# MazeBoard.net
KiCad netlist of a schematic drawn in EAGLE
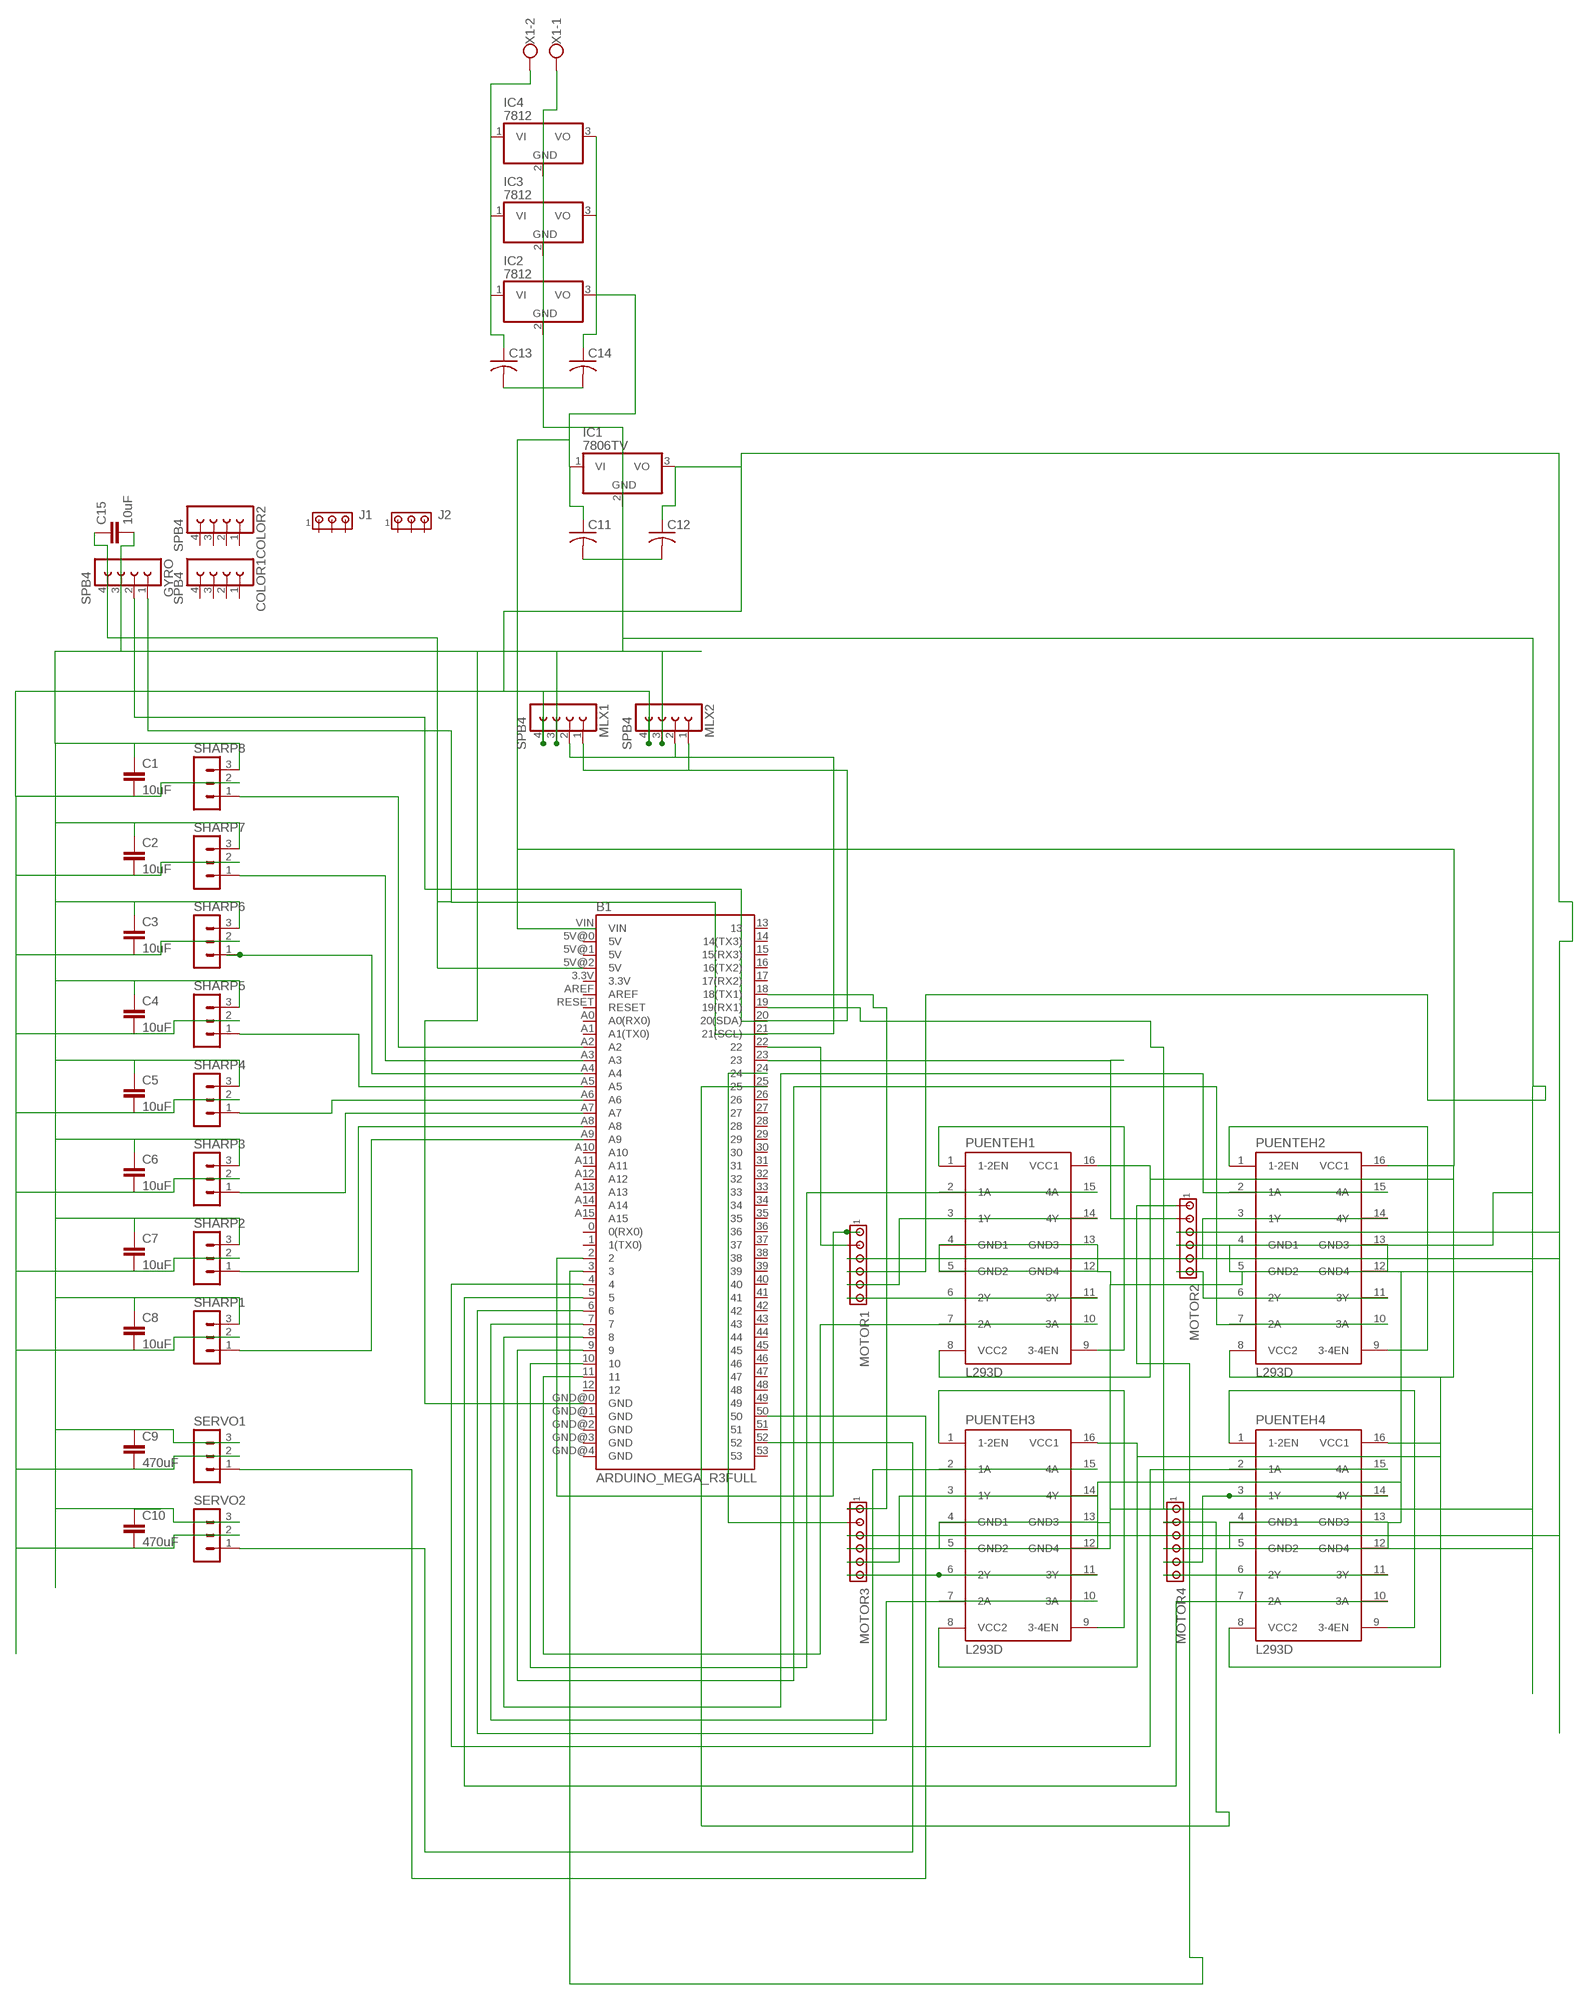
[diagram p0: schematic, sheet 1]

(export (version "E")
  (design (tool "Eeschema 10.0.6"))
  (components
    (comp (ref "B1")
      (value "ARDUINO_MEGA_R3FULL")
      (footprint "eagle-import:ARDUINO_MEGA")
      (libsource (lib "eagle-import") (part "ARDUINO_MEGA_R3FULL"))
    )
    (comp (ref "C1")
      (value "10uF")
      (footprint "eagle-import:C2.5-3")
      (libsource (lib "eagle-import") (part "C2,5-3"))
    )
    (comp (ref "C2")
      (value "10uF")
      (footprint "eagle-import:C2.5-3")
      (libsource (lib "eagle-import") (part "C2,5-3"))
    )
    (comp (ref "C3")
      (value "10uF")
      (footprint "eagle-import:C2.5-3")
      (libsource (lib "eagle-import") (part "C2,5-3"))
    )
    (comp (ref "C4")
      (value "10uF")
      (footprint "eagle-import:C2.5-3")
      (libsource (lib "eagle-import") (part "C2,5-3"))
    )
    (comp (ref "C5")
      (value "10uF")
      (footprint "eagle-import:C2.5-3")
      (libsource (lib "eagle-import") (part "C2,5-3"))
    )
    (comp (ref "C6")
      (value "10uF")
      (footprint "eagle-import:C2.5-3")
      (libsource (lib "eagle-import") (part "C2,5-3"))
    )
    (comp (ref "C7")
      (value "10uF")
      (footprint "eagle-import:C2.5-3")
      (libsource (lib "eagle-import") (part "C2,5-3"))
    )
    (comp (ref "C8")
      (value "10uF")
      (footprint "eagle-import:C2.5-3")
      (libsource (lib "eagle-import") (part "C2,5-3"))
    )
    (comp (ref "C9")
      (value "470uF")
      (footprint "eagle-import:C2.5-3")
      (libsource (lib "eagle-import") (part "C2,5-3"))
    )
    (comp (ref "C10")
      (value "470uF")
      (footprint "eagle-import:C2.5-3")
      (libsource (lib "eagle-import") (part "C2,5-3"))
    )
    (comp (ref "C11")
      (value "C-US025-024X044")
      (footprint "eagle-import:C025-024X044")
      (libsource (lib "eagle-import") (part "C-US025-024X044"))
    )
    (comp (ref "C12")
      (value "C-US025-024X044")
      (footprint "eagle-import:C025-024X044")
      (libsource (lib "eagle-import") (part "C-US025-024X044"))
    )
    (comp (ref "C13")
      (value "C-US025-024X044")
      (footprint "eagle-import:C025-024X044")
      (libsource (lib "eagle-import") (part "C-US025-024X044"))
    )
    (comp (ref "C14")
      (value "C-US025-024X044")
      (footprint "eagle-import:C025-024X044")
      (libsource (lib "eagle-import") (part "C-US025-024X044"))
    )
    (comp (ref "C15")
      (value "10uF")
      (footprint "eagle-import:C2.5-3")
      (libsource (lib "eagle-import") (part "C2,5-3"))
    )
    (comp (ref "COLOR1")
      (value "SPB4")
      (footprint "eagle-import:SPB4")
      (libsource (lib "eagle-import") (part "SPB4"))
    )
    (comp (ref "COLOR2")
      (value "SPB4")
      (footprint "eagle-import:SPB4")
      (libsource (lib "eagle-import") (part "SPB4"))
    )
    (comp (ref "GYRO")
      (value "SPB4")
      (footprint "eagle-import:SPB4")
      (libsource (lib "eagle-import") (part "SPB4"))
    )
    (comp (ref "IC1")
      (value "7806TV")
      (footprint "eagle-import:TO220V")
      (libsource (lib "eagle-import") (part "78TV05"))
    )
    (comp (ref "IC2")
      (value "7812")
      (footprint "eagle-import:TO220V")
      (libsource (lib "eagle-import") (part "78TV05"))
    )
    (comp (ref "IC3")
      (value "7812")
      (footprint "eagle-import:TO220V")
      (libsource (lib "eagle-import") (part "78TV05"))
    )
    (comp (ref "IC4")
      (value "7812")
      (footprint "eagle-import:TO220V")
      (libsource (lib "eagle-import") (part "78TV05"))
    )
    (comp (ref "J1")
      (value "MTA03-100")
      (footprint "eagle-import:10X03MTA")
      (libsource (lib "eagle-import") (part "MTA03-100"))
    )
    (comp (ref "J2")
      (value "MTA03-100")
      (footprint "eagle-import:10X03MTA")
      (libsource (lib "eagle-import") (part "MTA03-100"))
    )
    (comp (ref "MLX1")
      (value "SPB4")
      (footprint "eagle-import:SPB4")
      (libsource (lib "eagle-import") (part "SPB4"))
    )
    (comp (ref "MLX2")
      (value "SPB4")
      (footprint "eagle-import:SPB4")
      (libsource (lib "eagle-import") (part "SPB4"))
    )
    (comp (ref "MOTOR1")
      (value "MTA06-100")
      (footprint "eagle-import:10X06MTA")
      (libsource (lib "eagle-import") (part "MTA06-100"))
    )
    (comp (ref "MOTOR2")
      (value "MTA06-100")
      (footprint "eagle-import:10X06MTA")
      (libsource (lib "eagle-import") (part "MTA06-100"))
    )
    (comp (ref "MOTOR3")
      (value "MTA06-100")
      (footprint "eagle-import:10X06MTA")
      (libsource (lib "eagle-import") (part "MTA06-100"))
    )
    (comp (ref "MOTOR4")
      (value "MTA06-100")
      (footprint "eagle-import:10X06MTA")
      (libsource (lib "eagle-import") (part "MTA06-100"))
    )
    (comp (ref "PUENTEH1")
      (value "L293D")
      (footprint "eagle-import:DIL16")
      (libsource (lib "eagle-import") (part "L293D"))
    )
    (comp (ref "PUENTEH2")
      (value "L293D")
      (footprint "eagle-import:DIL16")
      (libsource (lib "eagle-import") (part "L293D"))
    )
    (comp (ref "PUENTEH3")
      (value "L293D")
      (footprint "eagle-import:DIL16")
      (libsource (lib "eagle-import") (part "L293D"))
    )
    (comp (ref "PUENTEH4")
      (value "L293D")
      (footprint "eagle-import:DIL16")
      (libsource (lib "eagle-import") (part "L293D"))
    )
    (comp (ref "SERVO1")
      (value "MA03-1")
      (footprint "eagle-import:MA03-1")
      (libsource (lib "eagle-import") (part "MA03-1"))
    )
    (comp (ref "SERVO2")
      (value "MA03-1")
      (footprint "eagle-import:MA03-1")
      (libsource (lib "eagle-import") (part "MA03-1"))
    )
    (comp (ref "SHARP1")
      (value "MA03-1")
      (footprint "eagle-import:MA03-1")
      (libsource (lib "eagle-import") (part "MA03-1"))
    )
    (comp (ref "SHARP2")
      (value "MA03-1")
      (footprint "eagle-import:MA03-1")
      (libsource (lib "eagle-import") (part "MA03-1"))
    )
    (comp (ref "SHARP3")
      (value "MA03-1")
      (footprint "eagle-import:MA03-1")
      (libsource (lib "eagle-import") (part "MA03-1"))
    )
    (comp (ref "SHARP4")
      (value "MA03-1")
      (footprint "eagle-import:MA03-1")
      (libsource (lib "eagle-import") (part "MA03-1"))
    )
    (comp (ref "SHARP5")
      (value "MA03-1")
      (footprint "eagle-import:MA03-1")
      (libsource (lib "eagle-import") (part "MA03-1"))
    )
    (comp (ref "SHARP6")
      (value "MA03-1")
      (footprint "eagle-import:MA03-1")
      (libsource (lib "eagle-import") (part "MA03-1"))
    )
    (comp (ref "SHARP7")
      (value "MA03-1")
      (footprint "eagle-import:MA03-1")
      (libsource (lib "eagle-import") (part "MA03-1"))
    )
    (comp (ref "SHARP8")
      (value "MA03-1")
      (footprint "eagle-import:MA03-1")
      (libsource (lib "eagle-import") (part "MA03-1"))
    )
    (comp (ref "X1")
      (value "W237-102")
      (footprint "eagle-import:W237-102")
      (fields (field (name "MPN") "237-102"))
      (libsource (lib "eagle-import") (part "W237-102"))
    )
  )
  (nets
    (net (code "1") (name "Net-(B1-5V-Pad5V@2)") (class "Default")
      (node (ref "B1") (pin "5V@2") (pinfunction "5V_5V@2") (pintype "bidirectional"))
      (node (ref "C15") (pin "1") (pinfunction "1_1") (pintype "passive"))
      (node (ref "GYRO") (pin "4") (pinfunction "4_4") (pintype "passive"))
    )
    (net (code "2") (name "Net-(B1-18(TX1))") (class "Default")
      (node (ref "B1") (pin "18") (pinfunction "18(TX1)_18") (pintype "bidirectional"))
      (node (ref "MOTOR3") (pin "1") (pinfunction "1_1") (pintype "passive"))
    )
    (net (code "3") (name "Net-(B1-19(RX1))") (class "Default")
      (node (ref "B1") (pin "19") (pinfunction "19(RX1)_19") (pintype "bidirectional"))
      (node (ref "MOTOR4") (pin "1") (pinfunction "1_1") (pintype "passive"))
    )
    (net (code "4") (name "Net-(B1-20(SDA))") (class "Default")
      (node (ref "B1") (pin "20") (pinfunction "20(SDA)_20") (pintype "bidirectional"))
      (node (ref "GYRO") (pin "2") (pinfunction "2_2") (pintype "passive"))
      (node (ref "MLX1") (pin "1") (pinfunction "1_1") (pintype "passive"))
      (node (ref "MLX2") (pin "1") (pinfunction "1_1") (pintype "passive"))
    )
    (net (code "5") (name "Net-(B1-21(SCL))") (class "Default")
      (node (ref "B1") (pin "21") (pinfunction "21(SCL)_21") (pintype "bidirectional"))
      (node (ref "GYRO") (pin "1") (pinfunction "1_1") (pintype "passive"))
      (node (ref "MLX1") (pin "2") (pinfunction "2_2") (pintype "passive"))
      (node (ref "MLX2") (pin "2") (pinfunction "2_2") (pintype "passive"))
    )
    (net (code "6") (name "Net-(B1-Pad2)") (class "Default")
      (node (ref "B1") (pin "2") (pinfunction "2_2") (pintype "bidirectional"))
      (node (ref "MOTOR1") (pin "1") (pinfunction "1_1") (pintype "passive"))
    )
    (net (code "7") (name "Net-(B1-Pad3)") (class "Default")
      (node (ref "B1") (pin "3") (pinfunction "3_3") (pintype "bidirectional"))
      (node (ref "MOTOR2") (pin "1") (pinfunction "1_1") (pintype "passive"))
    )
    (net (code "8") (name "Net-(B1-Pad22)") (class "Default")
      (node (ref "B1") (pin "22") (pinfunction "22_22") (pintype "bidirectional"))
      (node (ref "MOTOR1") (pin "2") (pinfunction "2_2") (pintype "passive"))
    )
    (net (code "9") (name "Net-(B1-Pad23)") (class "Default")
      (node (ref "B1") (pin "23") (pinfunction "23_23") (pintype "bidirectional"))
      (node (ref "MOTOR2") (pin "2") (pinfunction "2_2") (pintype "passive"))
    )
    (net (code "10") (name "Net-(B1-Pad24)") (class "Default")
      (node (ref "B1") (pin "24") (pinfunction "24_24") (pintype "bidirectional"))
      (node (ref "MOTOR3") (pin "2") (pinfunction "2_2") (pintype "passive"))
    )
    (net (code "11") (name "Net-(B1-Pad25)") (class "Default")
      (node (ref "B1") (pin "25") (pinfunction "25_25") (pintype "bidirectional"))
      (node (ref "MOTOR4") (pin "2") (pinfunction "2_2") (pintype "passive"))
    )
    (net (code "12") (name "Net-(B1-Pad50)") (class "Default")
      (node (ref "B1") (pin "50") (pinfunction "50_50") (pintype "bidirectional"))
      (node (ref "SERVO1") (pin "1") (pinfunction "1_1") (pintype "passive"))
    )
    (net (code "13") (name "Net-(B1-Pad52)") (class "Default")
      (node (ref "B1") (pin "52") (pinfunction "52_52") (pintype "bidirectional"))
      (node (ref "SERVO2") (pin "1") (pinfunction "1_1") (pintype "passive"))
    )
    (net (code "14") (name "Net-(B1-PadA2)") (class "Default")
      (node (ref "B1") (pin "A2") (pinfunction "A2_A2") (pintype "bidirectional"))
      (node (ref "SHARP8") (pin "1") (pinfunction "1_1") (pintype "passive"))
    )
    (net (code "15") (name "Net-(B1-PadA3)") (class "Default")
      (node (ref "B1") (pin "A3") (pinfunction "A3_A3") (pintype "bidirectional"))
      (node (ref "SHARP7") (pin "1") (pinfunction "1_1") (pintype "passive"))
    )
    (net (code "16") (name "Net-(B1-PadA4)") (class "Default")
      (node (ref "B1") (pin "A4") (pinfunction "A4_A4") (pintype "bidirectional"))
      (node (ref "SHARP6") (pin "1") (pinfunction "1_1") (pintype "passive"))
    )
    (net (code "17") (name "Net-(B1-PadA5)") (class "Default")
      (node (ref "B1") (pin "A5") (pinfunction "A5_A5") (pintype "bidirectional"))
      (node (ref "SHARP5") (pin "1") (pinfunction "1_1") (pintype "passive"))
    )
    (net (code "18") (name "Net-(B1-PadA6)") (class "Default")
      (node (ref "B1") (pin "A6") (pinfunction "A6_A6") (pintype "bidirectional"))
      (node (ref "SHARP4") (pin "1") (pinfunction "1_1") (pintype "passive"))
    )
    (net (code "19") (name "Net-(B1-PadA7)") (class "Default")
      (node (ref "B1") (pin "A7") (pinfunction "A7_A7") (pintype "bidirectional"))
      (node (ref "SHARP3") (pin "1") (pinfunction "1_1") (pintype "passive"))
    )
    (net (code "20") (name "Net-(B1-PadA8)") (class "Default")
      (node (ref "B1") (pin "A8") (pinfunction "A8_A8") (pintype "bidirectional"))
      (node (ref "SHARP2") (pin "1") (pinfunction "1_1") (pintype "passive"))
    )
    (net (code "21") (name "Net-(B1-PadA9)") (class "Default")
      (node (ref "B1") (pin "A9") (pinfunction "A9_A9") (pintype "bidirectional"))
      (node (ref "SHARP1") (pin "1") (pinfunction "1_1") (pintype "passive"))
    )
    (net (code "22") (name "Net-(IC1-GND)") (class "Default")
      (node (ref "B1") (pin "GND@0") (pinfunction "GND_GND@0") (pintype "bidirectional"))
      (node (ref "C1") (pin "1") (pinfunction "1_1") (pintype "passive"))
      (node (ref "C10") (pin "1") (pinfunction "1_1") (pintype "passive"))
      (node (ref "C11") (pin "2") (pinfunction "2_2") (pintype "passive"))
      (node (ref "C12") (pin "2") (pinfunction "2_2") (pintype "passive"))
      (node (ref "C13") (pin "2") (pinfunction "2_2") (pintype "passive"))
      (node (ref "C14") (pin "2") (pinfunction "2_2") (pintype "passive"))
      (node (ref "C15") (pin "2") (pinfunction "2_2") (pintype "passive"))
      (node (ref "C2") (pin "1") (pinfunction "1_1") (pintype "passive"))
      (node (ref "C3") (pin "1") (pinfunction "1_1") (pintype "passive"))
      (node (ref "C4") (pin "1") (pinfunction "1_1") (pintype "passive"))
      (node (ref "C5") (pin "1") (pinfunction "1_1") (pintype "passive"))
      (node (ref "C6") (pin "1") (pinfunction "1_1") (pintype "passive"))
      (node (ref "C7") (pin "1") (pinfunction "1_1") (pintype "passive"))
      (node (ref "C8") (pin "1") (pinfunction "1_1") (pintype "passive"))
      (node (ref "C9") (pin "1") (pinfunction "1_1") (pintype "passive"))
      (node (ref "GYRO") (pin "3") (pinfunction "3_3") (pintype "passive"))
      (node (ref "IC1") (pin "2") (pinfunction "GND_2") (pintype "passive"))
      (node (ref "IC2") (pin "2") (pinfunction "GND_2") (pintype "passive"))
      (node (ref "IC3") (pin "2") (pinfunction "GND_2") (pintype "passive"))
      (node (ref "IC4") (pin "2") (pinfunction "GND_2") (pintype "passive"))
      (node (ref "MLX1") (pin "3") (pinfunction "3_3") (pintype "passive"))
      (node (ref "MLX2") (pin "3") (pinfunction "3_3") (pintype "passive"))
      (node (ref "MOTOR1") (pin "4") (pinfunction "4_4") (pintype "passive"))
      (node (ref "MOTOR2") (pin "4") (pinfunction "4_4") (pintype "passive"))
      (node (ref "MOTOR3") (pin "4") (pinfunction "4_4") (pintype "passive"))
      (node (ref "MOTOR4") (pin "4") (pinfunction "4_4") (pintype "passive"))
      (node (ref "PUENTEH1") (pin "12") (pinfunction "GND4_12") (pintype "power_in"))
      (node (ref "PUENTEH1") (pin "13") (pinfunction "GND3_13") (pintype "power_in"))
      (node (ref "PUENTEH1") (pin "4") (pinfunction "GND1_4") (pintype "power_in"))
      (node (ref "PUENTEH1") (pin "5") (pinfunction "GND2_5") (pintype "power_in"))
      (node (ref "PUENTEH2") (pin "12") (pinfunction "GND4_12") (pintype "power_in"))
      (node (ref "PUENTEH2") (pin "13") (pinfunction "GND3_13") (pintype "power_in"))
      (node (ref "PUENTEH2") (pin "4") (pinfunction "GND1_4") (pintype "power_in"))
      (node (ref "PUENTEH2") (pin "5") (pinfunction "GND2_5") (pintype "power_in"))
      (node (ref "PUENTEH3") (pin "12") (pinfunction "GND4_12") (pintype "power_in"))
      (node (ref "PUENTEH3") (pin "13") (pinfunction "GND3_13") (pintype "power_in"))
      (node (ref "PUENTEH3") (pin "4") (pinfunction "GND1_4") (pintype "power_in"))
      (node (ref "PUENTEH3") (pin "5") (pinfunction "GND2_5") (pintype "power_in"))
      (node (ref "PUENTEH4") (pin "12") (pinfunction "GND4_12") (pintype "power_in"))
      (node (ref "PUENTEH4") (pin "13") (pinfunction "GND3_13") (pintype "power_in"))
      (node (ref "PUENTEH4") (pin "4") (pinfunction "GND1_4") (pintype "power_in"))
      (node (ref "PUENTEH4") (pin "5") (pinfunction "GND2_5") (pintype "power_in"))
      (node (ref "SERVO1") (pin "3") (pinfunction "3_3") (pintype "passive"))
      (node (ref "SERVO2") (pin "3") (pinfunction "3_3") (pintype "passive"))
      (node (ref "SHARP1") (pin "3") (pinfunction "3_3") (pintype "passive"))
      (node (ref "SHARP2") (pin "3") (pinfunction "3_3") (pintype "passive"))
      (node (ref "SHARP3") (pin "3") (pinfunction "3_3") (pintype "passive"))
      (node (ref "SHARP4") (pin "3") (pinfunction "3_3") (pintype "passive"))
      (node (ref "SHARP5") (pin "3") (pinfunction "3_3") (pintype "passive"))
      (node (ref "SHARP6") (pin "3") (pinfunction "3_3") (pintype "passive"))
      (node (ref "SHARP7") (pin "3") (pinfunction "3_3") (pintype "passive"))
      (node (ref "SHARP8") (pin "3") (pinfunction "3_3") (pintype "passive"))
      (node (ref "X1") (pin "1") (pinfunction "KL_1") (pintype "passive"))
    )
    (net (code "23") (name "Net-(IC1-VI)") (class "Default")
      (node (ref "C11") (pin "1") (pinfunction "1_1") (pintype "passive"))
      (node (ref "C14") (pin "1") (pinfunction "1_1") (pintype "passive"))
      (node (ref "IC1") (pin "1") (pinfunction "VI_1") (pintype "input"))
      (node (ref "IC2") (pin "3") (pinfunction "VO_3") (pintype "passive"))
      (node (ref "IC3") (pin "3") (pinfunction "VO_3") (pintype "passive"))
      (node (ref "IC4") (pin "3") (pinfunction "VO_3") (pintype "passive"))
      (node (ref "PUENTEH1") (pin "16") (pinfunction "VCC1_16") (pintype "power_in"))
      (node (ref "PUENTEH1") (pin "8") (pinfunction "VCC2_8") (pintype "power_in"))
      (node (ref "PUENTEH2") (pin "16") (pinfunction "VCC1_16") (pintype "power_in"))
      (node (ref "PUENTEH2") (pin "8") (pinfunction "VCC2_8") (pintype "power_in"))
      (node (ref "PUENTEH3") (pin "16") (pinfunction "VCC1_16") (pintype "power_in"))
      (node (ref "PUENTEH3") (pin "8") (pinfunction "VCC2_8") (pintype "power_in"))
      (node (ref "PUENTEH4") (pin "16") (pinfunction "VCC1_16") (pintype "power_in"))
      (node (ref "PUENTEH4") (pin "8") (pinfunction "VCC2_8") (pintype "power_in"))
    )
    (net (code "24") (name "Net-(IC1-VO)") (class "Default")
      (node (ref "C1") (pin "2") (pinfunction "2_2") (pintype "passive"))
      (node (ref "C10") (pin "2") (pinfunction "2_2") (pintype "passive"))
      (node (ref "C12") (pin "1") (pinfunction "1_1") (pintype "passive"))
      (node (ref "C2") (pin "2") (pinfunction "2_2") (pintype "passive"))
      (node (ref "C3") (pin "2") (pinfunction "2_2") (pintype "passive"))
      (node (ref "C4") (pin "2") (pinfunction "2_2") (pintype "passive"))
      (node (ref "C5") (pin "2") (pinfunction "2_2") (pintype "passive"))
      (node (ref "C6") (pin "2") (pinfunction "2_2") (pintype "passive"))
      (node (ref "C7") (pin "2") (pinfunction "2_2") (pintype "passive"))
      (node (ref "C8") (pin "2") (pinfunction "2_2") (pintype "passive"))
      (node (ref "C9") (pin "2") (pinfunction "2_2") (pintype "passive"))
      (node (ref "IC1") (pin "3") (pinfunction "VO_3") (pintype "passive"))
      (node (ref "MLX1") (pin "4") (pinfunction "4_4") (pintype "passive"))
      (node (ref "MLX2") (pin "4") (pinfunction "4_4") (pintype "passive"))
      (node (ref "MOTOR1") (pin "3") (pinfunction "3_3") (pintype "passive"))
      (node (ref "MOTOR2") (pin "3") (pinfunction "3_3") (pintype "passive"))
      (node (ref "MOTOR3") (pin "3") (pinfunction "3_3") (pintype "passive"))
      (node (ref "MOTOR4") (pin "3") (pinfunction "3_3") (pintype "passive"))
      (node (ref "SERVO1") (pin "2") (pinfunction "2_2") (pintype "passive"))
      (node (ref "SERVO2") (pin "2") (pinfunction "2_2") (pintype "passive"))
      (node (ref "SHARP1") (pin "2") (pinfunction "2_2") (pintype "passive"))
      (node (ref "SHARP2") (pin "2") (pinfunction "2_2") (pintype "passive"))
      (node (ref "SHARP3") (pin "2") (pinfunction "2_2") (pintype "passive"))
      (node (ref "SHARP4") (pin "2") (pinfunction "2_2") (pintype "passive"))
      (node (ref "SHARP5") (pin "2") (pinfunction "2_2") (pintype "passive"))
      (node (ref "SHARP6") (pin "2") (pinfunction "2_2") (pintype "passive"))
      (node (ref "SHARP7") (pin "2") (pinfunction "2_2") (pintype "passive"))
      (node (ref "SHARP8") (pin "2") (pinfunction "2_2") (pintype "passive"))
    )
    (net (code "25") (name "Net-(IC2-VI)") (class "Default")
      (node (ref "C13") (pin "1") (pinfunction "1_1") (pintype "passive"))
      (node (ref "IC2") (pin "1") (pinfunction "VI_1") (pintype "input"))
      (node (ref "IC3") (pin "1") (pinfunction "VI_1") (pintype "input"))
      (node (ref "IC4") (pin "1") (pinfunction "VI_1") (pintype "input"))
      (node (ref "X1") (pin "2") (pinfunction "KL_2") (pintype "passive"))
    )
    (net (code "26") (name "Net-(PUENTEH1-1-2EN)") (class "Default")
      (node (ref "PUENTEH1") (pin "1") (pinfunction "1-2EN_1") (pintype "input"))
      (node (ref "PUENTEH1") (pin "9") (pinfunction "3-4EN_9") (pintype "input"))
    )
    (net (code "27") (name "Net-(PUENTEH1-1A)") (class "Default")
      (node (ref "B1") (pin "10") (pinfunction "10_10") (pintype "bidirectional"))
      (node (ref "PUENTEH1") (pin "15") (pinfunction "4A_15") (pintype "input"))
      (node (ref "PUENTEH1") (pin "2") (pinfunction "1A_2") (pintype "input"))
    )
    (net (code "28") (name "Net-(PUENTEH1-1Y)") (class "Default")
      (node (ref "MOTOR1") (pin "5") (pinfunction "5_5") (pintype "passive"))
      (node (ref "PUENTEH1") (pin "14") (pinfunction "4Y_14") (pintype "output"))
      (node (ref "PUENTEH1") (pin "3") (pinfunction "1Y_3") (pintype "output"))
    )
    (net (code "29") (name "Net-(PUENTEH1-2A)") (class "Default")
      (node (ref "B1") (pin "11") (pinfunction "11_11") (pintype "bidirectional"))
      (node (ref "PUENTEH1") (pin "10") (pinfunction "3A_10") (pintype "input"))
      (node (ref "PUENTEH1") (pin "7") (pinfunction "2A_7") (pintype "input"))
    )
    (net (code "30") (name "Net-(PUENTEH1-2Y)") (class "Default")
      (node (ref "MOTOR1") (pin "6") (pinfunction "6_6") (pintype "passive"))
      (node (ref "PUENTEH1") (pin "11") (pinfunction "3Y_11") (pintype "output"))
      (node (ref "PUENTEH1") (pin "6") (pinfunction "2Y_6") (pintype "output"))
    )
    (net (code "31") (name "Net-(PUENTEH2-1-2EN)") (class "Default")
      (node (ref "PUENTEH2") (pin "1") (pinfunction "1-2EN_1") (pintype "input"))
      (node (ref "PUENTEH2") (pin "9") (pinfunction "3-4EN_9") (pintype "input"))
    )
    (net (code "32") (name "Net-(PUENTEH2-1A)") (class "Default")
      (node (ref "B1") (pin "8") (pinfunction "8_8") (pintype "bidirectional"))
      (node (ref "PUENTEH2") (pin "15") (pinfunction "4A_15") (pintype "input"))
      (node (ref "PUENTEH2") (pin "2") (pinfunction "1A_2") (pintype "input"))
    )
    (net (code "33") (name "Net-(PUENTEH2-1Y)") (class "Default")
      (node (ref "MOTOR2") (pin "5") (pinfunction "5_5") (pintype "passive"))
      (node (ref "PUENTEH2") (pin "14") (pinfunction "4Y_14") (pintype "output"))
      (node (ref "PUENTEH2") (pin "3") (pinfunction "1Y_3") (pintype "output"))
    )
    (net (code "34") (name "Net-(PUENTEH2-2A)") (class "Default")
      (node (ref "B1") (pin "9") (pinfunction "9_9") (pintype "bidirectional"))
      (node (ref "PUENTEH2") (pin "10") (pinfunction "3A_10") (pintype "input"))
      (node (ref "PUENTEH2") (pin "7") (pinfunction "2A_7") (pintype "input"))
    )
    (net (code "35") (name "Net-(PUENTEH2-2Y)") (class "Default")
      (node (ref "MOTOR2") (pin "6") (pinfunction "6_6") (pintype "passive"))
      (node (ref "PUENTEH2") (pin "11") (pinfunction "3Y_11") (pintype "output"))
      (node (ref "PUENTEH2") (pin "6") (pinfunction "2Y_6") (pintype "output"))
    )
    (net (code "36") (name "Net-(PUENTEH3-1-2EN)") (class "Default")
      (node (ref "PUENTEH3") (pin "1") (pinfunction "1-2EN_1") (pintype "input"))
      (node (ref "PUENTEH3") (pin "9") (pinfunction "3-4EN_9") (pintype "input"))
    )
    (net (code "37") (name "Net-(PUENTEH3-1A)") (class "Default")
      (node (ref "B1") (pin "6") (pinfunction "6_6") (pintype "bidirectional"))
      (node (ref "PUENTEH3") (pin "15") (pinfunction "4A_15") (pintype "input"))
      (node (ref "PUENTEH3") (pin "2") (pinfunction "1A_2") (pintype "input"))
    )
    (net (code "38") (name "Net-(PUENTEH3-1Y)") (class "Default")
      (node (ref "MOTOR3") (pin "5") (pinfunction "5_5") (pintype "passive"))
      (node (ref "PUENTEH3") (pin "14") (pinfunction "4Y_14") (pintype "output"))
      (node (ref "PUENTEH3") (pin "3") (pinfunction "1Y_3") (pintype "output"))
    )
    (net (code "39") (name "Net-(PUENTEH3-2A)") (class "Default")
      (node (ref "B1") (pin "7") (pinfunction "7_7") (pintype "bidirectional"))
      (node (ref "PUENTEH3") (pin "10") (pinfunction "3A_10") (pintype "input"))
      (node (ref "PUENTEH3") (pin "7") (pinfunction "2A_7") (pintype "input"))
    )
    (net (code "40") (name "Net-(PUENTEH3-2Y)") (class "Default")
      (node (ref "MOTOR3") (pin "6") (pinfunction "6_6") (pintype "passive"))
      (node (ref "PUENTEH3") (pin "11") (pinfunction "3Y_11") (pintype "output"))
      (node (ref "PUENTEH3") (pin "6") (pinfunction "2Y_6") (pintype "output"))
    )
    (net (code "41") (name "Net-(PUENTEH4-1-2EN)") (class "Default")
      (node (ref "PUENTEH4") (pin "1") (pinfunction "1-2EN_1") (pintype "input"))
      (node (ref "PUENTEH4") (pin "9") (pinfunction "3-4EN_9") (pintype "input"))
    )
    (net (code "42") (name "Net-(PUENTEH4-1A)") (class "Default")
      (node (ref "B1") (pin "4") (pinfunction "4_4") (pintype "bidirectional"))
      (node (ref "PUENTEH4") (pin "15") (pinfunction "4A_15") (pintype "input"))
      (node (ref "PUENTEH4") (pin "2") (pinfunction "1A_2") (pintype "input"))
    )
    (net (code "43") (name "Net-(PUENTEH4-1Y)") (class "Default")
      (node (ref "MOTOR4") (pin "5") (pinfunction "5_5") (pintype "passive"))
      (node (ref "PUENTEH4") (pin "14") (pinfunction "4Y_14") (pintype "output"))
      (node (ref "PUENTEH4") (pin "3") (pinfunction "1Y_3") (pintype "output"))
    )
    (net (code "44") (name "Net-(PUENTEH4-2A)") (class "Default")
      (node (ref "B1") (pin "5") (pinfunction "5_5") (pintype "bidirectional"))
      (node (ref "PUENTEH4") (pin "10") (pinfunction "3A_10") (pintype "input"))
      (node (ref "PUENTEH4") (pin "7") (pinfunction "2A_7") (pintype "input"))
    )
    (net (code "45") (name "Net-(PUENTEH4-2Y)") (class "Default")
      (node (ref "MOTOR4") (pin "6") (pinfunction "6_6") (pintype "passive"))
      (node (ref "PUENTEH4") (pin "11") (pinfunction "3Y_11") (pintype "output"))
      (node (ref "PUENTEH4") (pin "6") (pinfunction "2Y_6") (pintype "output"))
    )
    (net (code "46") (name "unconnected-(B1-0(RX0)-Pad0)") (class "Default")
      (node (ref "B1") (pin "0") (pinfunction "0(RX0)_0") (pintype "bidirectional"))
    )
    (net (code "47") (name "unconnected-(B1-1(TX0)-Pad1)") (class "Default")
      (node (ref "B1") (pin "1") (pinfunction "1(TX0)_1") (pintype "bidirectional"))
    )
    (net (code "48") (name "unconnected-(B1-5V-Pad5V@0)") (class "Default")
      (node (ref "B1") (pin "5V@0") (pinfunction "5V_5V@0") (pintype "bidirectional"))
    )
    (net (code "49") (name "unconnected-(B1-5V-Pad5V@1)") (class "Default")
      (node (ref "B1") (pin "5V@1") (pinfunction "5V_5V@1") (pintype "bidirectional"))
    )
    (net (code "50") (name "unconnected-(B1-14(TX3)-Pad14)") (class "Default")
      (node (ref "B1") (pin "14") (pinfunction "14(TX3)_14") (pintype "bidirectional"))
    )
    (net (code "51") (name "unconnected-(B1-15(RX3)-Pad15)") (class "Default")
      (node (ref "B1") (pin "15") (pinfunction "15(RX3)_15") (pintype "bidirectional"))
    )
    (net (code "52") (name "unconnected-(B1-16(TX2)-Pad16)") (class "Default")
      (node (ref "B1") (pin "16") (pinfunction "16(TX2)_16") (pintype "bidirectional"))
    )
    (net (code "53") (name "unconnected-(B1-17(RX2)-Pad17)") (class "Default")
      (node (ref "B1") (pin "17") (pinfunction "17(RX2)_17") (pintype "bidirectional"))
    )
    (net (code "54") (name "unconnected-(B1-A0(RX0)-PadA0)") (class "Default")
      (node (ref "B1") (pin "A0") (pinfunction "A0(RX0)_A0") (pintype "bidirectional"))
    )
    (net (code "55") (name "unconnected-(B1-A1(TX0)-PadA1)") (class "Default")
      (node (ref "B1") (pin "A1") (pinfunction "A1(TX0)_A1") (pintype "bidirectional"))
    )
    (net (code "56") (name "unconnected-(B1-GND-PadGND@1)") (class "Default")
      (node (ref "B1") (pin "GND@1") (pinfunction "GND_GND@1") (pintype "bidirectional"))
    )
    (net (code "57") (name "unconnected-(B1-GND-PadGND@2)") (class "Default")
      (node (ref "B1") (pin "GND@2") (pinfunction "GND_GND@2") (pintype "bidirectional"))
    )
    (net (code "58") (name "unconnected-(B1-GND-PadGND@3)") (class "Default")
      (node (ref "B1") (pin "GND@3") (pinfunction "GND_GND@3") (pintype "bidirectional"))
    )
    (net (code "59") (name "unconnected-(B1-GND-PadGND@4)") (class "Default")
      (node (ref "B1") (pin "GND@4") (pinfunction "GND_GND@4") (pintype "bidirectional"))
    )
    (net (code "60") (name "unconnected-(B1-Pad3.3V)") (class "Default")
      (node (ref "B1") (pin "3.3V") (pinfunction "3.3V_3.3V") (pintype "bidirectional"))
    )
    (net (code "61") (name "unconnected-(B1-Pad12)") (class "Default")
      (node (ref "B1") (pin "12") (pinfunction "12_12") (pintype "bidirectional"))
    )
    (net (code "62") (name "unconnected-(B1-Pad13)") (class "Default")
      (node (ref "B1") (pin "13") (pinfunction "13_13") (pintype "bidirectional"))
    )
    (net (code "63") (name "unconnected-(B1-Pad26)") (class "Default")
      (node (ref "B1") (pin "26") (pinfunction "26_26") (pintype "bidirectional"))
    )
    (net (code "64") (name "unconnected-(B1-Pad27)") (class "Default")
      (node (ref "B1") (pin "27") (pinfunction "27_27") (pintype "bidirectional"))
    )
    (net (code "65") (name "unconnected-(B1-Pad28)") (class "Default")
      (node (ref "B1") (pin "28") (pinfunction "28_28") (pintype "bidirectional"))
    )
    (net (code "66") (name "unconnected-(B1-Pad29)") (class "Default")
      (node (ref "B1") (pin "29") (pinfunction "29_29") (pintype "bidirectional"))
    )
    (net (code "67") (name "unconnected-(B1-Pad30)") (class "Default")
      (node (ref "B1") (pin "30") (pinfunction "30_30") (pintype "bidirectional"))
    )
    (net (code "68") (name "unconnected-(B1-Pad31)") (class "Default")
      (node (ref "B1") (pin "31") (pinfunction "31_31") (pintype "bidirectional"))
    )
    (net (code "69") (name "unconnected-(B1-Pad32)") (class "Default")
      (node (ref "B1") (pin "32") (pinfunction "32_32") (pintype "bidirectional"))
    )
    (net (code "70") (name "unconnected-(B1-Pad33)") (class "Default")
      (node (ref "B1") (pin "33") (pinfunction "33_33") (pintype "bidirectional"))
    )
    (net (code "71") (name "unconnected-(B1-Pad34)") (class "Default")
      (node (ref "B1") (pin "34") (pinfunction "34_34") (pintype "bidirectional"))
    )
    (net (code "72") (name "unconnected-(B1-Pad35)") (class "Default")
      (node (ref "B1") (pin "35") (pinfunction "35_35") (pintype "bidirectional"))
    )
    (net (code "73") (name "unconnected-(B1-Pad36)") (class "Default")
      (node (ref "B1") (pin "36") (pinfunction "36_36") (pintype "bidirectional"))
    )
    (net (code "74") (name "unconnected-(B1-Pad37)") (class "Default")
      (node (ref "B1") (pin "37") (pinfunction "37_37") (pintype "bidirectional"))
    )
    (net (code "75") (name "unconnected-(B1-Pad38)") (class "Default")
      (node (ref "B1") (pin "38") (pinfunction "38_38") (pintype "bidirectional"))
    )
    (net (code "76") (name "unconnected-(B1-Pad39)") (class "Default")
      (node (ref "B1") (pin "39") (pinfunction "39_39") (pintype "bidirectional"))
    )
    (net (code "77") (name "unconnected-(B1-Pad40)") (class "Default")
      (node (ref "B1") (pin "40") (pinfunction "40_40") (pintype "bidirectional"))
    )
    (net (code "78") (name "unconnected-(B1-Pad41)") (class "Default")
      (node (ref "B1") (pin "41") (pinfunction "41_41") (pintype "bidirectional"))
    )
    (net (code "79") (name "unconnected-(B1-Pad42)") (class "Default")
      (node (ref "B1") (pin "42") (pinfunction "42_42") (pintype "bidirectional"))
    )
    (net (code "80") (name "unconnected-(B1-Pad43)") (class "Default")
      (node (ref "B1") (pin "43") (pinfunction "43_43") (pintype "bidirectional"))
    )
    (net (code "81") (name "unconnected-(B1-Pad44)") (class "Default")
      (node (ref "B1") (pin "44") (pinfunction "44_44") (pintype "bidirectional"))
    )
    (net (code "82") (name "unconnected-(B1-Pad45)") (class "Default")
      (node (ref "B1") (pin "45") (pinfunction "45_45") (pintype "bidirectional"))
    )
    (net (code "83") (name "unconnected-(B1-Pad46)") (class "Default")
      (node (ref "B1") (pin "46") (pinfunction "46_46") (pintype "bidirectional"))
    )
    (net (code "84") (name "unconnected-(B1-Pad47)") (class "Default")
      (node (ref "B1") (pin "47") (pinfunction "47_47") (pintype "bidirectional"))
    )
    (net (code "85") (name "unconnected-(B1-Pad48)") (class "Default")
      (node (ref "B1") (pin "48") (pinfunction "48_48") (pintype "bidirectional"))
    )
    (net (code "86") (name "unconnected-(B1-Pad49)") (class "Default")
      (node (ref "B1") (pin "49") (pinfunction "49_49") (pintype "bidirectional"))
    )
    (net (code "87") (name "unconnected-(B1-Pad51)") (class "Default")
      (node (ref "B1") (pin "51") (pinfunction "51_51") (pintype "bidirectional"))
    )
    (net (code "88") (name "unconnected-(B1-Pad53)") (class "Default")
      (node (ref "B1") (pin "53") (pinfunction "53_53") (pintype "bidirectional"))
    )
    (net (code "89") (name "unconnected-(B1-PadA10)") (class "Default")
      (node (ref "B1") (pin "A10") (pinfunction "A10_A10") (pintype "bidirectional"))
    )
    (net (code "90") (name "unconnected-(B1-PadA11)") (class "Default")
      (node (ref "B1") (pin "A11") (pinfunction "A11_A11") (pintype "bidirectional"))
    )
    (net (code "91") (name "unconnected-(B1-PadA12)") (class "Default")
      (node (ref "B1") (pin "A12") (pinfunction "A12_A12") (pintype "bidirectional"))
    )
    (net (code "92") (name "unconnected-(B1-PadA13)") (class "Default")
      (node (ref "B1") (pin "A13") (pinfunction "A13_A13") (pintype "bidirectional"))
    )
    (net (code "93") (name "unconnected-(B1-PadA14)") (class "Default")
      (node (ref "B1") (pin "A14") (pinfunction "A14_A14") (pintype "bidirectional"))
    )
    (net (code "94") (name "unconnected-(B1-PadA15)") (class "Default")
      (node (ref "B1") (pin "A15") (pinfunction "A15_A15") (pintype "bidirectional"))
    )
    (net (code "95") (name "unconnected-(B1-PadAREF)") (class "Default")
      (node (ref "B1") (pin "AREF") (pinfunction "AREF_AREF") (pintype "bidirectional"))
    )
    (net (code "96") (name "unconnected-(B1-PadRESET)") (class "Default")
      (node (ref "B1") (pin "RESET") (pinfunction "RESET_RESET") (pintype "bidirectional"))
    )
    (net (code "97") (name "unconnected-(B1-PadVIN)") (class "Default")
      (node (ref "B1") (pin "VIN") (pinfunction "VIN_VIN") (pintype "bidirectional"))
    )
    (net (code "98") (name "unconnected-(COLOR1-Pad1)") (class "Default")
      (node (ref "COLOR1") (pin "1") (pinfunction "1_1") (pintype "passive"))
    )
    (net (code "99") (name "unconnected-(COLOR1-Pad2)") (class "Default")
      (node (ref "COLOR1") (pin "2") (pinfunction "2_2") (pintype "passive"))
    )
    (net (code "100") (name "unconnected-(COLOR1-Pad3)") (class "Default")
      (node (ref "COLOR1") (pin "3") (pinfunction "3_3") (pintype "passive"))
    )
    (net (code "101") (name "unconnected-(COLOR1-Pad4)") (class "Default")
      (node (ref "COLOR1") (pin "4") (pinfunction "4_4") (pintype "passive"))
    )
    (net (code "102") (name "unconnected-(COLOR2-Pad1)") (class "Default")
      (node (ref "COLOR2") (pin "1") (pinfunction "1_1") (pintype "passive"))
    )
    (net (code "103") (name "unconnected-(COLOR2-Pad2)") (class "Default")
      (node (ref "COLOR2") (pin "2") (pinfunction "2_2") (pintype "passive"))
    )
    (net (code "104") (name "unconnected-(COLOR2-Pad3)") (class "Default")
      (node (ref "COLOR2") (pin "3") (pinfunction "3_3") (pintype "passive"))
    )
    (net (code "105") (name "unconnected-(COLOR2-Pad4)") (class "Default")
      (node (ref "COLOR2") (pin "4") (pinfunction "4_4") (pintype "passive"))
    )
    (net (code "106") (name "unconnected-(J1-Pad1)") (class "Default")
      (node (ref "J1") (pin "1") (pinfunction "1_1") (pintype "passive"))
    )
    (net (code "107") (name "unconnected-(J1-Pad2)") (class "Default")
      (node (ref "J1") (pin "2") (pinfunction "2_2") (pintype "passive"))
    )
    (net (code "108") (name "unconnected-(J1-Pad3)") (class "Default")
      (node (ref "J1") (pin "3") (pinfunction "3_3") (pintype "passive"))
    )
    (net (code "109") (name "unconnected-(J2-Pad1)") (class "Default")
      (node (ref "J2") (pin "1") (pinfunction "1_1") (pintype "passive"))
    )
    (net (code "110") (name "unconnected-(J2-Pad2)") (class "Default")
      (node (ref "J2") (pin "2") (pinfunction "2_2") (pintype "passive"))
    )
    (net (code "111") (name "unconnected-(J2-Pad3)") (class "Default")
      (node (ref "J2") (pin "3") (pinfunction "3_3") (pintype "passive"))
    )
  )
)
